# Uav_V1.net
KiCad netlist of a schematic drawn in Altium Designer
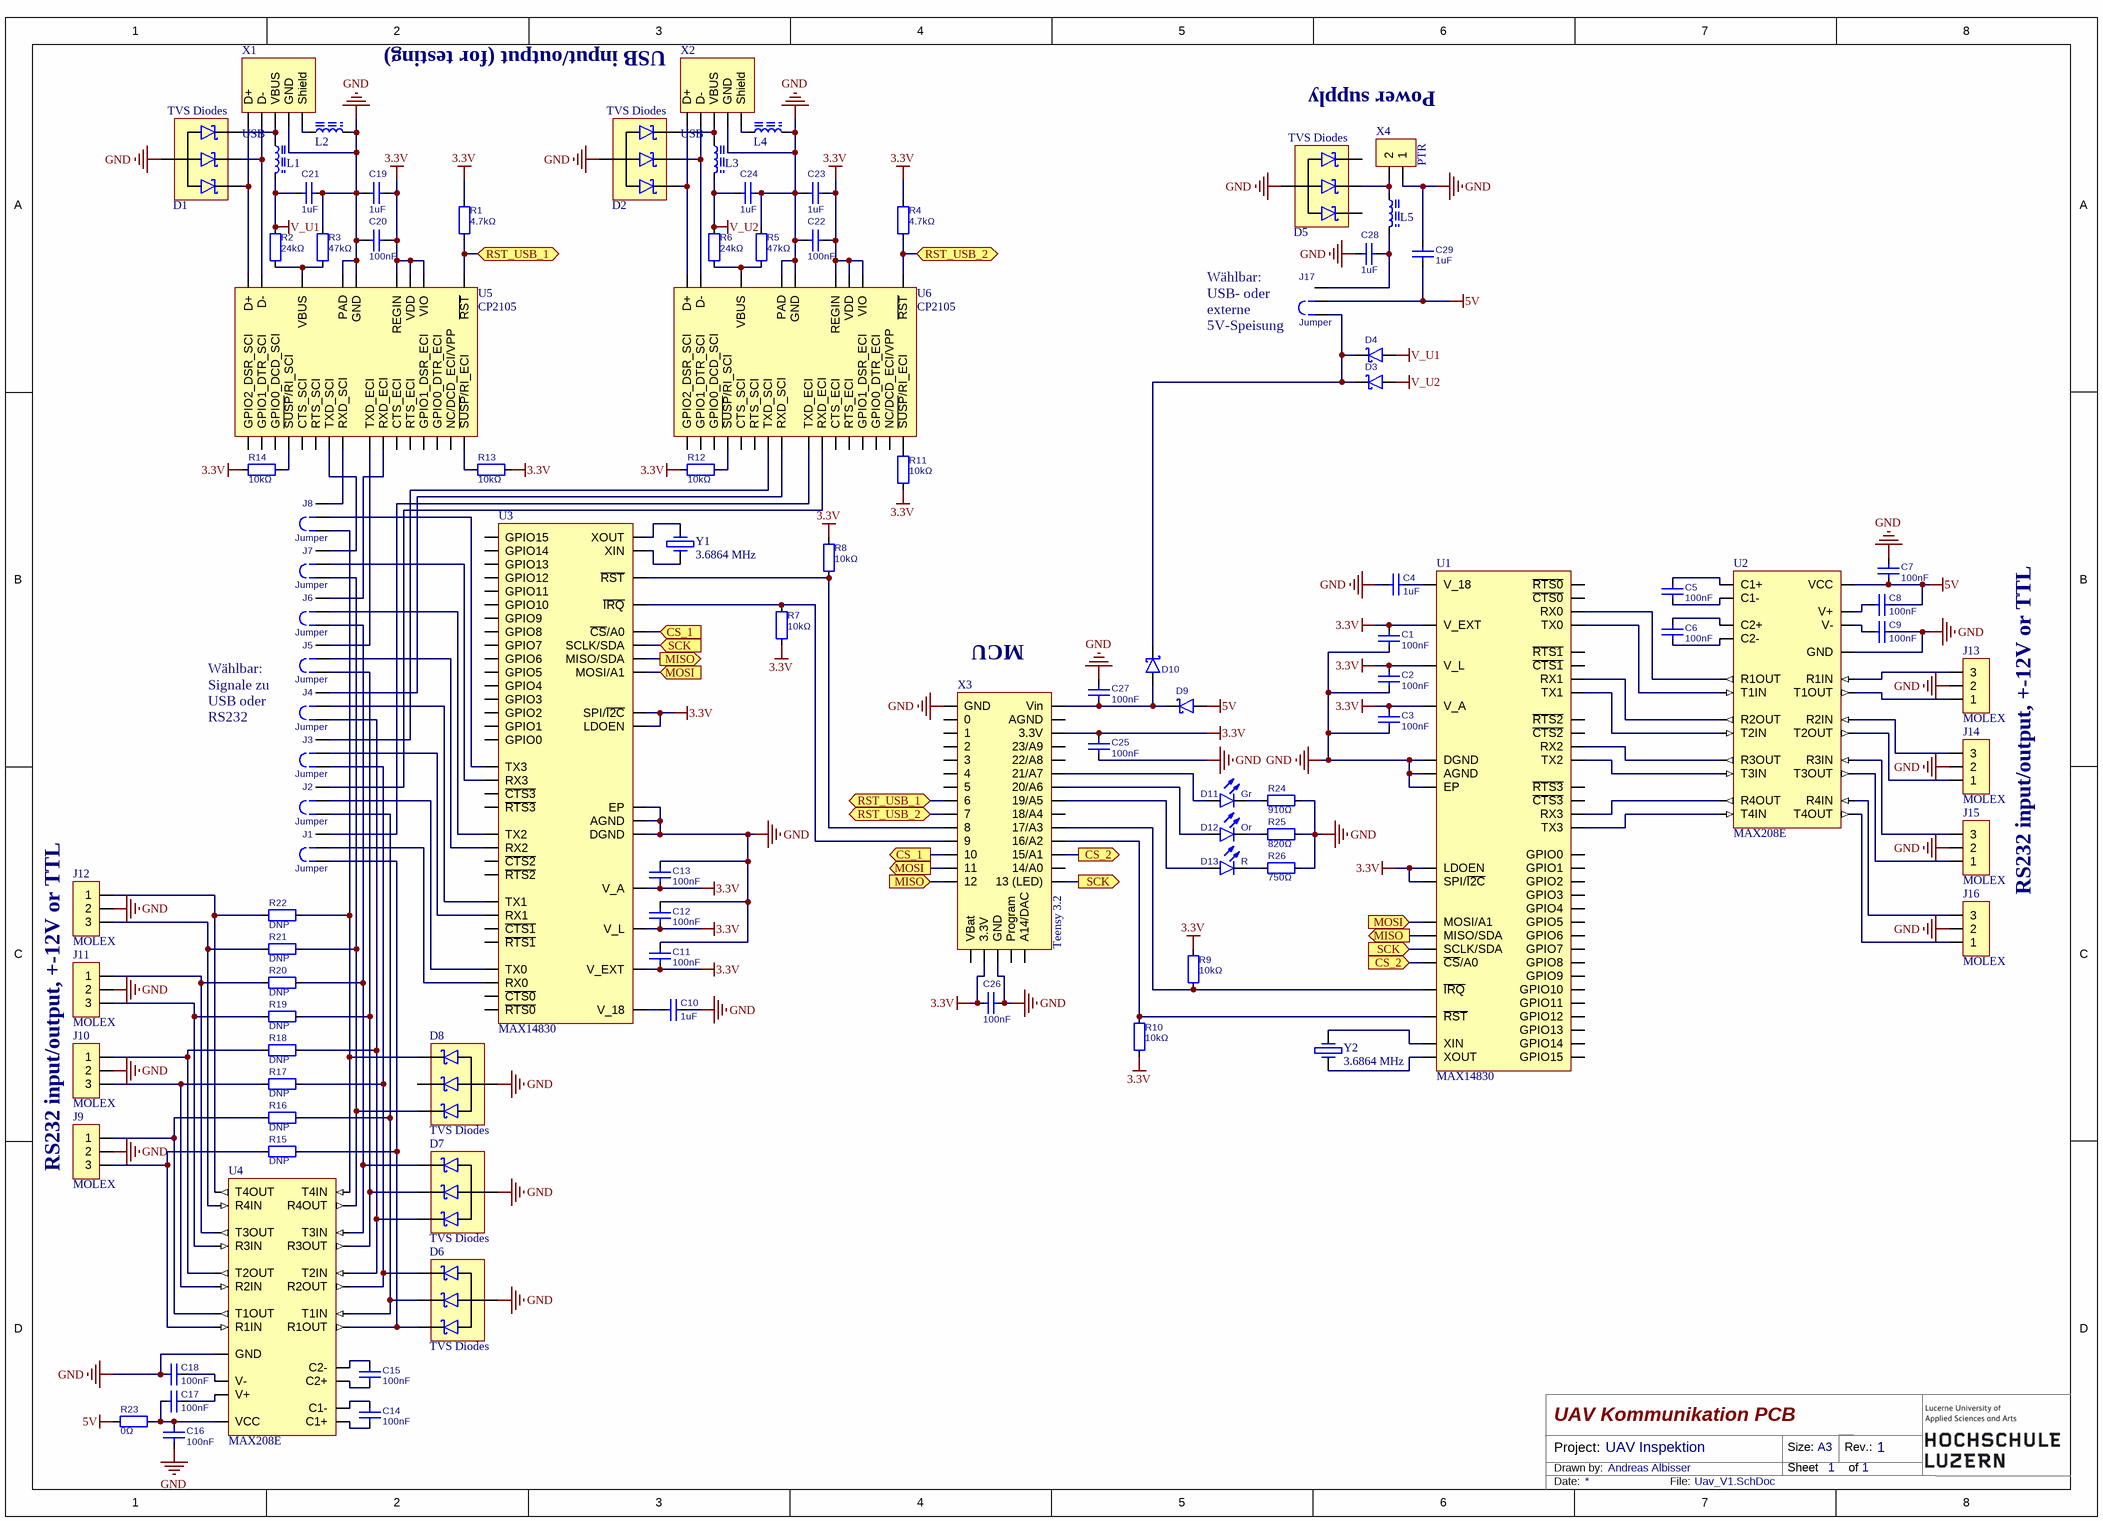
[diagram p0: Uav_V1.SchDoc]

(export (version "E")
  (design (tool "Eeschema 10.0.6"))
  (components
    (comp (ref "C1")
      (value "100nF")
      (footprint "0603")
      (description "Keramikkondensator 0603")
      (fields (field (name "CHANGED BY") "taalbiss"))
      (libsource (lib "CCE_Database_Libs") (part "C_Normal"))
    )
    (comp (ref "C2")
      (value "100nF")
      (footprint "0603")
      (description "Keramikkondensator 0603")
      (fields (field (name "CHANGED BY") "taalbiss"))
      (libsource (lib "CCE_Database_Libs") (part "C_Normal"))
    )
    (comp (ref "C3")
      (value "100nF")
      (footprint "0603")
      (description "Keramikkondensator 0603")
      (fields (field (name "CHANGED BY") "taalbiss"))
      (libsource (lib "CCE_Database_Libs") (part "C_Normal"))
    )
    (comp (ref "C4")
      (value "1uF")
      (footprint "0603")
      (description "Keramikkondensator 0603")
      (fields (field (name "CHANGED BY") "taalbiss"))
      (libsource (lib "CCE_Database_Libs") (part "C_Normal"))
    )
    (comp (ref "C5")
      (value "100nF")
      (footprint "0603")
      (description "Keramikkondensator 0603")
      (fields (field (name "CHANGED BY") "taalbiss"))
      (libsource (lib "CCE_Database_Libs") (part "C_Normal"))
    )
    (comp (ref "C6")
      (value "100nF")
      (footprint "0603")
      (description "Keramikkondensator 0603")
      (fields (field (name "CHANGED BY") "taalbiss"))
      (libsource (lib "CCE_Database_Libs") (part "C_Normal"))
    )
    (comp (ref "C7")
      (value "100nF")
      (footprint "0603")
      (description "Keramikkondensator 0603")
      (fields (field (name "CHANGED BY") "taalbiss"))
      (libsource (lib "CCE_Database_Libs") (part "C_Normal"))
    )
    (comp (ref "C8")
      (value "100nF")
      (footprint "0603")
      (description "Keramikkondensator 0603")
      (fields (field (name "CHANGED BY") "taalbiss"))
      (libsource (lib "CCE_Database_Libs") (part "C_Normal"))
    )
    (comp (ref "C9")
      (value "100nF")
      (footprint "0603")
      (description "Keramikkondensator 0603")
      (fields (field (name "CHANGED BY") "taalbiss"))
      (libsource (lib "CCE_Database_Libs") (part "C_Normal"))
    )
    (comp (ref "C10")
      (value "1uF")
      (footprint "0603")
      (description "Keramikkondensator 0603")
      (fields (field (name "CHANGED BY") "taalbiss"))
      (libsource (lib "CCE_Database_Libs") (part "C_Normal"))
    )
    (comp (ref "C11")
      (value "100nF")
      (footprint "0603")
      (description "Keramikkondensator 0603")
      (fields (field (name "CHANGED BY") "taalbiss"))
      (libsource (lib "CCE_Database_Libs") (part "C_Normal"))
    )
    (comp (ref "C12")
      (value "100nF")
      (footprint "0603")
      (description "Keramikkondensator 0603")
      (fields (field (name "CHANGED BY") "taalbiss"))
      (libsource (lib "CCE_Database_Libs") (part "C_Normal"))
    )
    (comp (ref "C13")
      (value "100nF")
      (footprint "0603")
      (description "Keramikkondensator 0603")
      (fields (field (name "CHANGED BY") "taalbiss"))
      (libsource (lib "CCE_Database_Libs") (part "C_Normal"))
    )
    (comp (ref "C14")
      (value "100nF")
      (footprint "0603")
      (description "Keramikkondensator 0603")
      (fields (field (name "CHANGED BY") "taalbiss"))
      (libsource (lib "CCE_Database_Libs") (part "C_Normal"))
    )
    (comp (ref "C15")
      (value "100nF")
      (footprint "0603")
      (description "Keramikkondensator 0603")
      (fields (field (name "CHANGED BY") "taalbiss"))
      (libsource (lib "CCE_Database_Libs") (part "C_Normal"))
    )
    (comp (ref "C16")
      (value "100nF")
      (footprint "0603")
      (description "Keramikkondensator 0603")
      (fields (field (name "CHANGED BY") "taalbiss"))
      (libsource (lib "CCE_Database_Libs") (part "C_Normal"))
    )
    (comp (ref "C17")
      (value "100nF")
      (footprint "0603")
      (description "Keramikkondensator 0603")
      (fields (field (name "CHANGED BY") "taalbiss"))
      (libsource (lib "CCE_Database_Libs") (part "C_Normal"))
    )
    (comp (ref "C18")
      (value "100nF")
      (footprint "0603")
      (description "Keramikkondensator 0603")
      (fields (field (name "CHANGED BY") "taalbiss"))
      (libsource (lib "CCE_Database_Libs") (part "C_Normal"))
    )
    (comp (ref "C19")
      (value "1uF")
      (footprint "0603")
      (description "Keramikkondensator 0603")
      (fields (field (name "CHANGED BY") "taalbiss"))
      (libsource (lib "CCE_Database_Libs") (part "C_Normal"))
    )
    (comp (ref "C20")
      (value "100nF")
      (footprint "0603")
      (description "Keramikkondensator 0603")
      (fields (field (name "CHANGED BY") "taalbiss"))
      (libsource (lib "CCE_Database_Libs") (part "C_Normal"))
    )
    (comp (ref "C21")
      (value "1uF")
      (footprint "0603")
      (description "Keramikkondensator 0603")
      (fields (field (name "CHANGED BY") "taalbiss"))
      (libsource (lib "CCE_Database_Libs") (part "C_Normal"))
    )
    (comp (ref "C22")
      (value "100nF")
      (footprint "0603")
      (description "Keramikkondensator 0603")
      (fields (field (name "CHANGED BY") "taalbiss"))
      (libsource (lib "CCE_Database_Libs") (part "C_Normal"))
    )
    (comp (ref "C23")
      (value "1uF")
      (footprint "0603")
      (description "Keramikkondensator 0603")
      (fields (field (name "CHANGED BY") "taalbiss"))
      (libsource (lib "CCE_Database_Libs") (part "C_Normal"))
    )
    (comp (ref "C24")
      (value "1uF")
      (footprint "0603")
      (description "Keramikkondensator 0603")
      (fields (field (name "CHANGED BY") "taalbiss"))
      (libsource (lib "CCE_Database_Libs") (part "C_Normal"))
    )
    (comp (ref "C25")
      (value "100nF")
      (footprint "0603")
      (description "Keramikkondensator 0603")
      (fields (field (name "CHANGED BY") "taalbiss"))
      (libsource (lib "CCE_Database_Libs") (part "C_Normal"))
    )
    (comp (ref "C26")
      (value "100nF")
      (footprint "0603")
      (description "Keramikkondensator 0603")
      (fields (field (name "CHANGED BY") "taalbiss"))
      (libsource (lib "CCE_Database_Libs") (part "C_Normal"))
    )
    (comp (ref "C27")
      (value "100nF")
      (footprint "0603")
      (description "Keramikkondensator 0603")
      (fields (field (name "CHANGED BY") "taalbiss"))
      (libsource (lib "CCE_Database_Libs") (part "C_Normal"))
    )
    (comp (ref "C28")
      (value "1uF")
      (footprint "0603")
      (description "Keramikkondensator 0603")
      (fields (field (name "CHANGED BY") "taalbiss"))
      (libsource (lib "CCE_Database_Libs") (part "C_Normal"))
    )
    (comp (ref "C29")
      (value "1uF")
      (footprint "0603")
      (description "Keramikkondensator 0603")
      (fields (field (name "CHANGED BY") "taalbiss"))
      (libsource (lib "CCE_Database_Libs") (part "C_Normal"))
    )
    (comp (ref "D1")
      (value "TVS Diodes")
      (footprint "UAV:SOT-143-4")
      (libsource (lib "") (part "TVS_Diode_3fach_1"))
    )
    (comp (ref "D2")
      (value "TVS Diodes")
      (footprint "UAV:SOT-143-4")
      (libsource (lib "") (part "TVS_Diode_3fach_1"))
    )
    (comp (ref "D3")
      (value "?")
      (footprint "SOD-123")
      (description "Schottky Diode SOD-123")
      (fields (field (name "CHANGED BY") "taalbiss"))
      (libsource (lib "CCE_Database_Libs") (part "Diode_Schottky"))
    )
    (comp (ref "D4")
      (value "?")
      (footprint "SOD-123")
      (description "Schottky Diode SOD-123")
      (fields (field (name "CHANGED BY") "taalbiss"))
      (libsource (lib "CCE_Database_Libs") (part "Diode_Schottky"))
    )
    (comp (ref "D5")
      (value "TVS Diodes")
      (footprint "UAV:SOT-143-4")
      (libsource (lib "") (part "TVS_Diode_3fach_1"))
    )
    (comp (ref "D6")
      (value "TVS Diodes")
      (footprint "UAV:SOT-143-4")
      (libsource (lib "UAV") (part "TVS_Diode_3fach"))
    )
    (comp (ref "D7")
      (value "TVS Diodes")
      (footprint "UAV:SOT-143-4")
      (libsource (lib "UAV") (part "TVS_Diode_3fach"))
    )
    (comp (ref "D8")
      (value "TVS Diodes")
      (footprint "UAV:SOT-143-4")
      (libsource (lib "UAV") (part "TVS_Diode_3fach"))
    )
    (comp (ref "D9")
      (value "?")
      (footprint "SOD-123")
      (description "Schottky Diode SOD-123")
      (fields (field (name "CHANGED BY") "taalbiss"))
      (libsource (lib "CCE_Database_Libs") (part "Diode_Schottky"))
    )
    (comp (ref "D10")
      (value "?")
      (footprint "SOD-123")
      (description "Schottky Diode SOD-123")
      (fields (field (name "CHANGED BY") "taalbiss"))
      (libsource (lib "CCE_Database_Libs") (part "Diode_Schottky"))
    )
    (comp (ref "D11")
      (value "Gr")
      (footprint "0603D")
      (description "LED SMD 0603")
      (fields (field (name "CHANGED BY") "taalbiss"))
      (libsource (lib "CCE_Database_Libs") (part "LED"))
    )
    (comp (ref "D12")
      (value "Or")
      (footprint "0603D")
      (description "LED SMD 0603")
      (fields (field (name "CHANGED BY") "taalbiss"))
      (libsource (lib "CCE_Database_Libs") (part "LED"))
    )
    (comp (ref "D13")
      (value "R")
      (footprint "0603D")
      (description "LED SMD 0603")
      (fields (field (name "CHANGED BY") "taalbiss"))
      (libsource (lib "CCE_Database_Libs") (part "LED"))
    )
    (comp (ref "J1")
      (value "Jumper")
      (footprint "Header2,54mm_1x3")
      (description "Jumper THT 2.54mm 1x3")
      (fields (field (name "CHANGED BY") "taalbiss"))
      (libsource (lib "CCE_Database_Libs") (part "Jumper_1x3"))
    )
    (comp (ref "J2")
      (value "Jumper")
      (footprint "Header2,54mm_1x3")
      (description "Jumper THT 2.54mm 1x3")
      (fields (field (name "CHANGED BY") "taalbiss"))
      (libsource (lib "CCE_Database_Libs") (part "Jumper_1x3"))
    )
    (comp (ref "J3")
      (value "Jumper")
      (footprint "Header2,54mm_1x3")
      (description "Jumper THT 2.54mm 1x3")
      (fields (field (name "CHANGED BY") "taalbiss"))
      (libsource (lib "CCE_Database_Libs") (part "Jumper_1x3"))
    )
    (comp (ref "J4")
      (value "Jumper")
      (footprint "Header2,54mm_1x3")
      (description "Jumper THT 2.54mm 1x3")
      (fields (field (name "CHANGED BY") "taalbiss"))
      (libsource (lib "CCE_Database_Libs") (part "Jumper_1x3"))
    )
    (comp (ref "J5")
      (value "Jumper")
      (footprint "Header2,54mm_1x3")
      (description "Jumper THT 2.54mm 1x3")
      (fields (field (name "CHANGED BY") "taalbiss"))
      (libsource (lib "CCE_Database_Libs") (part "Jumper_1x3"))
    )
    (comp (ref "J6")
      (value "Jumper")
      (footprint "Header2,54mm_1x3")
      (description "Jumper THT 2.54mm 1x3")
      (fields (field (name "CHANGED BY") "taalbiss"))
      (libsource (lib "CCE_Database_Libs") (part "Jumper_1x3"))
    )
    (comp (ref "J7")
      (value "Jumper")
      (footprint "Header2,54mm_1x3")
      (description "Jumper THT 2.54mm 1x3")
      (fields (field (name "CHANGED BY") "taalbiss"))
      (libsource (lib "CCE_Database_Libs") (part "Jumper_1x3"))
    )
    (comp (ref "J8")
      (value "Jumper")
      (footprint "Header2,54mm_1x3")
      (description "Jumper THT 2.54mm 1x3")
      (fields (field (name "CHANGED BY") "taalbiss"))
      (libsource (lib "CCE_Database_Libs") (part "Jumper_1x3"))
    )
    (comp (ref "J9") (value "MOLEX") (footprint "UAV:MOLEX_1x3") (libsource (lib "") (part "Header_1x3_1")))
    (comp (ref "J10") (value "MOLEX") (footprint "UAV:MOLEX_1x3") (libsource (lib "") (part "Header_1x3_1")))
    (comp (ref "J11") (value "MOLEX") (footprint "UAV:MOLEX_1x3") (libsource (lib "") (part "Header_1x3_1")))
    (comp (ref "J12") (value "MOLEX") (footprint "UAV:MOLEX_1x3") (libsource (lib "") (part "Header_1x3_1")))
    (comp (ref "J13") (value "MOLEX") (footprint "UAV:MOLEX_1x3") (libsource (lib "UAV") (part "Header_1x3")))
    (comp (ref "J14") (value "MOLEX") (footprint "UAV:MOLEX_1x3") (libsource (lib "UAV") (part "Header_1x3")))
    (comp (ref "J15") (value "MOLEX") (footprint "UAV:MOLEX_1x3") (libsource (lib "UAV") (part "Header_1x3")))
    (comp (ref "J16") (value "MOLEX") (footprint "UAV:MOLEX_1x3") (libsource (lib "UAV") (part "Header_1x3")))
    (comp (ref "J17")
      (value "Jumper")
      (footprint "Header2,54mm_1x3")
      (description "Jumper THT 2.54mm 1x3")
      (fields (field (name "CHANGED BY") "taalbiss"))
      (libsource (lib "CCE_Database_Libs") (part "Jumper_1x3"))
    )
    (comp (ref "L1")
      (value "MPZ1608S601A")
      (footprint "0603")
      (description "Ferrit 0603")
      (fields (field (name "CHANGED BY") "taalbiss"))
      (libsource (lib "CCE_Database_Libs") (part "L_Ferrite"))
    )
    (comp (ref "L2")
      (value "MPZ1608S601A")
      (footprint "0603")
      (description "Ferrit 0603")
      (fields (field (name "CHANGED BY") "taalbiss"))
      (libsource (lib "CCE_Database_Libs") (part "L_Ferrite"))
    )
    (comp (ref "L3")
      (value "MPZ1608S601A")
      (footprint "0603")
      (description "Ferrit 0603")
      (fields (field (name "CHANGED BY") "taalbiss"))
      (libsource (lib "CCE_Database_Libs") (part "L_Ferrite"))
    )
    (comp (ref "L4")
      (value "MPZ1608S601A")
      (footprint "0603")
      (description "Ferrit 0603")
      (fields (field (name "CHANGED BY") "taalbiss"))
      (libsource (lib "CCE_Database_Libs") (part "L_Ferrite"))
    )
    (comp (ref "L5")
      (value "MPZ1608S601A")
      (footprint "0603")
      (description "Ferrit 0603")
      (fields (field (name "CHANGED BY") "taalbiss"))
      (libsource (lib "CCE_Database_Libs") (part "L_Ferrite"))
    )
    (comp (ref "R1")
      (value "4.7kΩ")
      (footprint "0603")
      (description "Widerstand 0603")
      (fields (field (name "CHANGED BY") "taalbiss"))
      (libsource (lib "") (part "R_Normal_1"))
    )
    (comp (ref "R2")
      (value "24kΩ")
      (footprint "0603")
      (description "Widerstand 0603")
      (fields (field (name "CHANGED BY") "taalbiss"))
      (libsource (lib "CCE_Database_Libs") (part "R_Normal"))
    )
    (comp (ref "R3")
      (value "47kΩ")
      (footprint "0603")
      (description "Widerstand 0603")
      (fields (field (name "CHANGED BY") "taalbiss"))
      (libsource (lib "CCE_Database_Libs") (part "R_Normal"))
    )
    (comp (ref "R4")
      (value "4.7kΩ")
      (footprint "0603")
      (description "Widerstand 0603")
      (fields (field (name "CHANGED BY") "taalbiss"))
      (libsource (lib "") (part "R_Normal_1"))
    )
    (comp (ref "R5")
      (value "47kΩ")
      (footprint "0603")
      (description "Widerstand 0603")
      (fields (field (name "CHANGED BY") "taalbiss"))
      (libsource (lib "CCE_Database_Libs") (part "R_Normal"))
    )
    (comp (ref "R6")
      (value "24kΩ")
      (footprint "0603")
      (description "Widerstand 0603")
      (fields (field (name "CHANGED BY") "taalbiss"))
      (libsource (lib "CCE_Database_Libs") (part "R_Normal"))
    )
    (comp (ref "R7")
      (value "10kΩ")
      (footprint "0603")
      (description "Widerstand 0603")
      (fields (field (name "CHANGED BY") "taalbiss"))
      (libsource (lib "") (part "R_Normal_1"))
    )
    (comp (ref "R8")
      (value "10kΩ")
      (footprint "0603")
      (description "Widerstand 0603")
      (fields (field (name "CHANGED BY") "taalbiss"))
      (libsource (lib "") (part "R_Normal_1"))
    )
    (comp (ref "R9")
      (value "10kΩ")
      (footprint "0603")
      (description "Widerstand 0603")
      (fields (field (name "CHANGED BY") "taalbiss"))
      (libsource (lib "") (part "R_Normal_1"))
    )
    (comp (ref "R10")
      (value "10kΩ")
      (footprint "0603")
      (description "Widerstand 0603")
      (fields (field (name "CHANGED BY") "taalbiss"))
      (libsource (lib "") (part "R_Normal_1"))
    )
    (comp (ref "R11")
      (value "10kΩ")
      (footprint "0603")
      (description "Widerstand 0603")
      (fields (field (name "CHANGED BY") "taalbiss"))
      (libsource (lib "") (part "R_Normal_1"))
    )
    (comp (ref "R12")
      (value "10kΩ")
      (footprint "0603")
      (description "Widerstand 0603")
      (fields (field (name "CHANGED BY") "taalbiss"))
      (libsource (lib "") (part "R_Normal_2"))
    )
    (comp (ref "R13")
      (value "10kΩ")
      (footprint "0603")
      (description "Widerstand 0603")
      (fields (field (name "CHANGED BY") "taalbiss"))
      (libsource (lib "") (part "R_Normal_2"))
    )
    (comp (ref "R14")
      (value "10kΩ")
      (footprint "0603")
      (description "Widerstand 0603")
      (fields (field (name "CHANGED BY") "taalbiss"))
      (libsource (lib "") (part "R_Normal_2"))
    )
    (comp (ref "R15")
      (value "DNP")
      (footprint "0603")
      (description "Widerstand 0603")
      (fields (field (name "CHANGED BY") "taalbiss"))
      (libsource (lib "") (part "R_Normal_2"))
    )
    (comp (ref "R16")
      (value "DNP")
      (footprint "0603")
      (description "Widerstand 0603")
      (fields (field (name "CHANGED BY") "taalbiss"))
      (libsource (lib "") (part "R_Normal_2"))
    )
    (comp (ref "R17")
      (value "DNP")
      (footprint "0603")
      (description "Widerstand 0603")
      (fields (field (name "CHANGED BY") "taalbiss"))
      (libsource (lib "") (part "R_Normal_2"))
    )
    (comp (ref "R18")
      (value "DNP")
      (footprint "0603")
      (description "Widerstand 0603")
      (fields (field (name "CHANGED BY") "taalbiss"))
      (libsource (lib "") (part "R_Normal_2"))
    )
    (comp (ref "R19")
      (value "DNP")
      (footprint "0603")
      (description "Widerstand 0603")
      (fields (field (name "CHANGED BY") "taalbiss"))
      (libsource (lib "") (part "R_Normal_2"))
    )
    (comp (ref "R20")
      (value "DNP")
      (footprint "0603")
      (description "Widerstand 0603")
      (fields (field (name "CHANGED BY") "taalbiss"))
      (libsource (lib "") (part "R_Normal_2"))
    )
    (comp (ref "R21")
      (value "DNP")
      (footprint "0603")
      (description "Widerstand 0603")
      (fields (field (name "CHANGED BY") "taalbiss"))
      (libsource (lib "") (part "R_Normal_2"))
    )
    (comp (ref "R22")
      (value "DNP")
      (footprint "0603")
      (description "Widerstand 0603")
      (fields (field (name "CHANGED BY") "taalbiss"))
      (libsource (lib "") (part "R_Normal_2"))
    )
    (comp (ref "R23")
      (value "0Ω")
      (footprint "0603")
      (description "Widerstand 0603")
      (fields (field (name "CHANGED BY") "taalbiss"))
      (libsource (lib "") (part "R_Normal_2"))
    )
    (comp (ref "R24")
      (value "910Ω")
      (footprint "0603")
      (description "Widerstand 0603")
      (fields (field (name "CHANGED BY") "taalbiss"))
      (libsource (lib "") (part "R_Normal_2"))
    )
    (comp (ref "R25")
      (value "820Ω")
      (footprint "0603")
      (description "Widerstand 0603")
      (fields (field (name "CHANGED BY") "taalbiss"))
      (libsource (lib "") (part "R_Normal_2"))
    )
    (comp (ref "R26")
      (value "750Ω")
      (footprint "0603")
      (description "Widerstand 0603")
      (fields (field (name "CHANGED BY") "taalbiss"))
      (libsource (lib "") (part "R_Normal_2"))
    )
    (comp (ref "U1") (value "MAX14830") (footprint "UAV:TQFN48") (libsource (lib "UAV") (part "MAX14830")))
    (comp (ref "U2") (value "MAX208E") (footprint "UAV:SSOP24") (libsource (lib "UAV") (part "MAX208E")))
    (comp (ref "U3") (value "MAX14830") (footprint "UAV:TQFN48") (libsource (lib "") (part "MAX14830_1")))
    (comp (ref "U4") (value "MAX208E") (footprint "UAV:SSOP24") (libsource (lib "") (part "MAX208E_1")))
    (comp (ref "U5") (value "CP2105") (footprint "UAV:QFN24") (libsource (lib "UAV") (part "CP2105")))
    (comp (ref "U6") (value "CP2105") (footprint "UAV:QFN24") (libsource (lib "UAV") (part "CP2105")))
    (comp (ref "X1") (value "USB") (footprint "UAV:USB_Mini_TypB") (libsource (lib "UAV") (part "USB")))
    (comp (ref "X2") (value "USB") (footprint "UAV:USB_Mini_TypB") (libsource (lib "UAV") (part "USB")))
    (comp (ref "X3")
      (value "Teensy 3.2")
      (footprint "UAV:Teensy_3_2")
      (libsource (lib "UAV") (part "Teensy_3_2"))
    )
    (comp (ref "X4") (value "PTR") (footprint "UAV:PTR_1X2") (libsource (lib "UAV") (part "Header_1x2")))
    (comp (ref "Y1")
      (value "3.6864 MHz")
      (footprint "UAV:Crystal_10x4_5mm")
      (libsource (lib "UAV") (part "Crystal_3_6864_MHz"))
    )
    (comp (ref "Y2")
      (value "3.6864 MHz")
      (footprint "UAV:Crystal_10x4_5mm")
      (libsource (lib "UAV") (part "Crystal_3_6864_MHz"))
    )
  )
  (nets
    (net (code "1") (name "/CS_1") (class "Default")
      (node (ref "U3") (pin "5") (pinfunction "~{CS}/A0_5") (pintype "passive"))
      (node (ref "X3") (pin "10") (pinfunction "10_10") (pintype "passive"))
    )
    (net (code "2") (name "/CS_2") (class "Default")
      (node (ref "U1") (pin "5") (pinfunction "~{CS}/A0_5") (pintype "passive"))
      (node (ref "X3") (pin "15") (pinfunction "15/A1_15") (pintype "passive"))
    )
    (net (code "3") (name "/MISO") (class "Default")
      (node (ref "U1") (pin "3") (pinfunction "MISO/SDA_3") (pintype "passive"))
      (node (ref "U3") (pin "3") (pinfunction "MISO/SDA_3") (pintype "passive"))
      (node (ref "X3") (pin "12") (pinfunction "12_12") (pintype "passive"))
    )
    (net (code "4") (name "/MOSI") (class "Default")
      (node (ref "U1") (pin "6") (pinfunction "MOSI/A1_6") (pintype "passive"))
      (node (ref "U3") (pin "6") (pinfunction "MOSI/A1_6") (pintype "passive"))
      (node (ref "X3") (pin "11") (pinfunction "11_11") (pintype "passive"))
    )
    (net (code "5") (name "/RST_USB_1") (class "Default")
      (node (ref "R1") (pin "1") (pinfunction "1_1") (pintype "passive"))
      (node (ref "U5") (pin "9") (pinfunction "~{RST}_9") (pintype "passive"))
      (node (ref "X3") (pin "6") (pinfunction "6_6") (pintype "passive"))
    )
    (net (code "6") (name "/RST_USB_2") (class "Default")
      (node (ref "R4") (pin "1") (pinfunction "1_1") (pintype "passive"))
      (node (ref "U6") (pin "9") (pinfunction "~{RST}_9") (pintype "passive"))
      (node (ref "X3") (pin "7") (pinfunction "7_7") (pintype "passive"))
    )
    (net (code "7") (name "/SCK") (class "Default")
      (node (ref "U1") (pin "4") (pinfunction "SCLK/SDA_4") (pintype "passive"))
      (node (ref "U3") (pin "4") (pinfunction "SCLK/SDA_4") (pintype "passive"))
      (node (ref "X3") (pin "13") (pinfunction "13_(LED)_13") (pintype "passive"))
    )
    (net (code "8") (name "3.3V") (class "Default")
      (node (ref "C1") (pin "2") (pinfunction "2_2") (pintype "passive"))
      (node (ref "C11") (pin "2") (pinfunction "2_2") (pintype "passive"))
      (node (ref "C12") (pin "2") (pinfunction "2_2") (pintype "passive"))
      (node (ref "C13") (pin "2") (pinfunction "2_2") (pintype "passive"))
      (node (ref "C19") (pin "1") (pinfunction "1_1") (pintype "passive"))
      (node (ref "C2") (pin "2") (pinfunction "2_2") (pintype "passive"))
      (node (ref "C20") (pin "1") (pinfunction "1_1") (pintype "passive"))
      (node (ref "C22") (pin "1") (pinfunction "1_1") (pintype "passive"))
      (node (ref "C23") (pin "1") (pinfunction "1_1") (pintype "passive"))
      (node (ref "C25") (pin "1") (pinfunction "1_1") (pintype "passive"))
      (node (ref "C26") (pin "1") (pinfunction "1_1") (pintype "passive"))
      (node (ref "C3") (pin "2") (pinfunction "2_2") (pintype "passive"))
      (node (ref "R1") (pin "2") (pinfunction "2_2") (pintype "passive"))
      (node (ref "R10") (pin "1") (pinfunction "1_1") (pintype "passive"))
      (node (ref "R11") (pin "1") (pinfunction "1_1") (pintype "passive"))
      (node (ref "R12") (pin "2") (pinfunction "2_2") (pintype "passive"))
      (node (ref "R13") (pin "1") (pinfunction "1_1") (pintype "passive"))
      (node (ref "R14") (pin "2") (pinfunction "2_2") (pintype "passive"))
      (node (ref "R4") (pin "2") (pinfunction "2_2") (pintype "passive"))
      (node (ref "R7") (pin "1") (pinfunction "1_1") (pintype "passive"))
      (node (ref "R8") (pin "2") (pinfunction "2_2") (pintype "passive"))
      (node (ref "R9") (pin "2") (pinfunction "2_2") (pintype "passive"))
      (node (ref "U1") (pin "1") (pinfunction "SPI/~{I2C}_1") (pintype "passive"))
      (node (ref "U1") (pin "2") (pinfunction "LDOEN_2") (pintype "passive"))
      (node (ref "U1") (pin "43") (pinfunction "V_EXT_43") (pintype "passive"))
      (node (ref "U1") (pin "47") (pinfunction "V_A_47") (pintype "passive"))
      (node (ref "U1") (pin "9") (pinfunction "V_L_9") (pintype "passive"))
      (node (ref "U3") (pin "1") (pinfunction "SPI/~{I2C}_1") (pintype "passive"))
      (node (ref "U3") (pin "2") (pinfunction "LDOEN_2") (pintype "passive"))
      (node (ref "U3") (pin "43") (pinfunction "V_EXT_43") (pintype "passive"))
      (node (ref "U3") (pin "47") (pinfunction "V_A_47") (pintype "passive"))
      (node (ref "U3") (pin "9") (pinfunction "V_L_9") (pintype "passive"))
      (node (ref "U5") (pin "5") (pinfunction "VIO_5") (pintype "passive"))
      (node (ref "U5") (pin "6") (pinfunction "VDD_6") (pintype "passive"))
      (node (ref "U5") (pin "7") (pinfunction "REGIN_7") (pintype "passive"))
      (node (ref "U6") (pin "5") (pinfunction "VIO_5") (pintype "passive"))
      (node (ref "U6") (pin "6") (pinfunction "VDD_6") (pintype "passive"))
      (node (ref "U6") (pin "7") (pinfunction "REGIN_7") (pintype "passive"))
      (node (ref "X3") (pin "3.3V_1") (pinfunction "3.3V_3.3V_1") (pintype "passive"))
      (node (ref "X3") (pin "3.3V_2") (pinfunction "3.3V_3.3V_2") (pintype "passive"))
    )
    (net (code "9") (name "5V") (class "Default")
      (node (ref "C29") (pin "1") (pinfunction "1_1") (pintype "passive"))
      (node (ref "C7") (pin "1") (pinfunction "1_1") (pintype "passive"))
      (node (ref "C8") (pin "1") (pinfunction "1_1") (pintype "passive"))
      (node (ref "D9") (pin "1") (pinfunction "A_1") (pintype "passive"))
      (node (ref "J17") (pin "2") (pinfunction "2_2") (pintype "passive"))
      (node (ref "R23") (pin "2") (pinfunction "2_2") (pintype "passive"))
      (node (ref "U2") (pin "9") (pinfunction "VCC_9") (pintype "passive"))
    )
    (net (code "10") (name "GND") (class "Default")
      (node (ref "C1") (pin "1") (pinfunction "1_1") (pintype "passive"))
      (node (ref "C10") (pin "1") (pinfunction "1_1") (pintype "passive"))
      (node (ref "C11") (pin "1") (pinfunction "1_1") (pintype "passive"))
      (node (ref "C12") (pin "1") (pinfunction "1_1") (pintype "passive"))
      (node (ref "C13") (pin "1") (pinfunction "1_1") (pintype "passive"))
      (node (ref "C16") (pin "2") (pinfunction "2_2") (pintype "passive"))
      (node (ref "C18") (pin "1") (pinfunction "1_1") (pintype "passive"))
      (node (ref "C19") (pin "2") (pinfunction "2_2") (pintype "passive"))
      (node (ref "C2") (pin "1") (pinfunction "1_1") (pintype "passive"))
      (node (ref "C20") (pin "2") (pinfunction "2_2") (pintype "passive"))
      (node (ref "C21") (pin "1") (pinfunction "1_1") (pintype "passive"))
      (node (ref "C22") (pin "2") (pinfunction "2_2") (pintype "passive"))
      (node (ref "C23") (pin "2") (pinfunction "2_2") (pintype "passive"))
      (node (ref "C24") (pin "1") (pinfunction "1_1") (pintype "passive"))
      (node (ref "C25") (pin "2") (pinfunction "2_2") (pintype "passive"))
      (node (ref "C26") (pin "2") (pinfunction "2_2") (pintype "passive"))
      (node (ref "C27") (pin "1") (pinfunction "1_1") (pintype "passive"))
      (node (ref "C28") (pin "2") (pinfunction "2_2") (pintype "passive"))
      (node (ref "C29") (pin "2") (pinfunction "2_2") (pintype "passive"))
      (node (ref "C3") (pin "1") (pinfunction "1_1") (pintype "passive"))
      (node (ref "C4") (pin "1") (pinfunction "1_1") (pintype "passive"))
      (node (ref "C7") (pin "2") (pinfunction "2_2") (pintype "passive"))
      (node (ref "C9") (pin "1") (pinfunction "1_1") (pintype "passive"))
      (node (ref "D1") (pin "1") (pinfunction "CA_1") (pintype "passive"))
      (node (ref "D2") (pin "1") (pinfunction "CA_1") (pintype "passive"))
      (node (ref "D5") (pin "1") (pinfunction "CA_1") (pintype "passive"))
      (node (ref "D6") (pin "1") (pinfunction "CA_1") (pintype "passive"))
      (node (ref "D7") (pin "1") (pinfunction "CA_1") (pintype "passive"))
      (node (ref "D8") (pin "1") (pinfunction "CA_1") (pintype "passive"))
      (node (ref "J10") (pin "2") (pinfunction "2_2") (pintype "passive"))
      (node (ref "J11") (pin "2") (pinfunction "2_2") (pintype "passive"))
      (node (ref "J12") (pin "2") (pinfunction "2_2") (pintype "passive"))
      (node (ref "J13") (pin "2") (pinfunction "2_2") (pintype "passive"))
      (node (ref "J14") (pin "2") (pinfunction "2_2") (pintype "passive"))
      (node (ref "J15") (pin "2") (pinfunction "2_2") (pintype "passive"))
      (node (ref "J16") (pin "2") (pinfunction "2_2") (pintype "passive"))
      (node (ref "J9") (pin "2") (pinfunction "2_2") (pintype "passive"))
      (node (ref "L2") (pin "2") (pinfunction "2_2") (pintype "passive"))
      (node (ref "L4") (pin "2") (pinfunction "2_2") (pintype "passive"))
      (node (ref "R24") (pin "1") (pinfunction "1_1") (pintype "passive"))
      (node (ref "R25") (pin "1") (pinfunction "1_1") (pintype "passive"))
      (node (ref "R26") (pin "1") (pinfunction "1_1") (pintype "passive"))
      (node (ref "R3") (pin "1") (pinfunction "1_1") (pintype "passive"))
      (node (ref "R5") (pin "1") (pinfunction "1_1") (pintype "passive"))
      (node (ref "U1") (pin "10") (pinfunction "DGND_10") (pintype "passive"))
      (node (ref "U1") (pin "46") (pinfunction "AGND_46") (pintype "passive"))
      (node (ref "U1") (pin "49") (pinfunction "EP_49") (pintype "passive"))
      (node (ref "U2") (pin "8") (pinfunction "GND_8") (pintype "passive"))
      (node (ref "U3") (pin "10") (pinfunction "DGND_10") (pintype "passive"))
      (node (ref "U3") (pin "46") (pinfunction "AGND_46") (pintype "passive"))
      (node (ref "U3") (pin "49") (pinfunction "EP_49") (pintype "passive"))
      (node (ref "U4") (pin "8") (pinfunction "GND_8") (pintype "passive"))
      (node (ref "U5") (pin "2") (pinfunction "GND_2") (pintype "passive"))
      (node (ref "U5") (pin "25") (pinfunction "PAD_25") (pintype "passive"))
      (node (ref "U6") (pin "2") (pinfunction "GND_2") (pintype "passive"))
      (node (ref "U6") (pin "25") (pinfunction "PAD_25") (pintype "passive"))
      (node (ref "X1") (pin "4") (pinfunction "GND_4") (pintype "passive"))
      (node (ref "X2") (pin "4") (pinfunction "GND_4") (pintype "passive"))
      (node (ref "X3") (pin "GND_1") (pinfunction "GND_GND_1") (pintype "passive"))
      (node (ref "X3") (pin "GND_2") (pinfunction "GND_GND_2") (pintype "passive"))
      (node (ref "X4") (pin "1") (pinfunction "1_1") (pintype "passive"))
    )
    (net (code "11") (name "Net-(C28-Pad1)") (class "Default")
      (node (ref "C28") (pin "1") (pinfunction "1_1") (pintype "passive"))
      (node (ref "J17") (pin "3") (pinfunction "3_3") (pintype "passive"))
      (node (ref "L5") (pin "2") (pinfunction "2_2") (pintype "passive"))
    )
    (net (code "12") (name "Net-(D1-K1)") (class "Default")
      (node (ref "D1") (pin "2") (pinfunction "K1_2") (pintype "passive"))
      (node (ref "U5") (pin "3") (pinfunction "D+_3") (pintype "passive"))
      (node (ref "X1") (pin "3") (pinfunction "D+_3") (pintype "passive"))
    )
    (net (code "13") (name "Net-(D1-K2)") (class "Default")
      (node (ref "D1") (pin "3") (pinfunction "K2_3") (pintype "passive"))
      (node (ref "U5") (pin "4") (pinfunction "D-_4") (pintype "passive"))
      (node (ref "X1") (pin "2") (pinfunction "D-_2") (pintype "passive"))
    )
    (net (code "14") (name "Net-(D1-K3)") (class "Default")
      (node (ref "D1") (pin "4") (pinfunction "K3_4") (pintype "passive"))
      (node (ref "L1") (pin "1") (pinfunction "1_1") (pintype "passive"))
      (node (ref "X1") (pin "1") (pinfunction "VBUS_1") (pintype "passive"))
    )
    (net (code "15") (name "Net-(D2-K1)") (class "Default")
      (node (ref "D2") (pin "2") (pinfunction "K1_2") (pintype "passive"))
      (node (ref "U6") (pin "3") (pinfunction "D+_3") (pintype "passive"))
      (node (ref "X2") (pin "3") (pinfunction "D+_3") (pintype "passive"))
    )
    (net (code "16") (name "Net-(D2-K2)") (class "Default")
      (node (ref "D2") (pin "3") (pinfunction "K2_3") (pintype "passive"))
      (node (ref "U6") (pin "4") (pinfunction "D-_4") (pintype "passive"))
      (node (ref "X2") (pin "2") (pinfunction "D-_2") (pintype "passive"))
    )
    (net (code "17") (name "Net-(D2-K3)") (class "Default")
      (node (ref "D2") (pin "4") (pinfunction "K3_4") (pintype "passive"))
      (node (ref "L3") (pin "1") (pinfunction "1_1") (pintype "passive"))
      (node (ref "X2") (pin "1") (pinfunction "VBUS_1") (pintype "passive"))
    )
    (net (code "18") (name "Net-(D5-K2)") (class "Default")
      (node (ref "D5") (pin "3") (pinfunction "K2_3") (pintype "passive"))
      (node (ref "L5") (pin "1") (pinfunction "1_1") (pintype "passive"))
      (node (ref "X4") (pin "2") (pinfunction "2_2") (pintype "passive"))
    )
    (net (code "19") (name "Net-(D6-K1)") (class "Default")
      (node (ref "D6") (pin "2") (pinfunction "K1_2") (pintype "passive"))
      (node (ref "J3") (pin "1") (pinfunction "1_1") (pintype "passive"))
      (node (ref "R17") (pin "1") (pinfunction "1_1") (pintype "passive"))
      (node (ref "U4") (pin "4") (pinfunction "R2OUT_4") (pintype "output"))
    )
    (net (code "20") (name "Net-(D6-K2)") (class "Default")
      (node (ref "D6") (pin "3") (pinfunction "K2_3") (pintype "passive"))
      (node (ref "J2") (pin "1") (pinfunction "1_1") (pintype "passive"))
      (node (ref "R16") (pin "1") (pinfunction "1_1") (pintype "passive"))
      (node (ref "U4") (pin "5") (pinfunction "T1IN_5") (pintype "input"))
    )
    (net (code "21") (name "Net-(D6-K3)") (class "Default")
      (node (ref "D6") (pin "4") (pinfunction "K3_4") (pintype "passive"))
      (node (ref "J1") (pin "1") (pinfunction "1_1") (pintype "passive"))
      (node (ref "R15") (pin "1") (pinfunction "1_1") (pintype "passive"))
      (node (ref "U4") (pin "6") (pinfunction "R1OUT_6") (pintype "output"))
    )
    (net (code "22") (name "Net-(D7-K1)") (class "Default")
      (node (ref "D7") (pin "2") (pinfunction "K1_2") (pintype "passive"))
      (node (ref "J6") (pin "1") (pinfunction "1_1") (pintype "passive"))
      (node (ref "R20") (pin "1") (pinfunction "1_1") (pintype "passive"))
      (node (ref "U4") (pin "19") (pinfunction "T3IN_19") (pintype "input"))
    )
    (net (code "23") (name "Net-(D7-K2)") (class "Default")
      (node (ref "D7") (pin "3") (pinfunction "K2_3") (pintype "passive"))
      (node (ref "J5") (pin "1") (pinfunction "1_1") (pintype "passive"))
      (node (ref "R19") (pin "1") (pinfunction "1_1") (pintype "passive"))
      (node (ref "U4") (pin "22") (pinfunction "R3OUT_22") (pintype "output"))
    )
    (net (code "24") (name "Net-(D7-K3)") (class "Default")
      (node (ref "D7") (pin "4") (pinfunction "K3_4") (pintype "passive"))
      (node (ref "J4") (pin "1") (pinfunction "1_1") (pintype "passive"))
      (node (ref "R18") (pin "1") (pinfunction "1_1") (pintype "passive"))
      (node (ref "U4") (pin "18") (pinfunction "T2IN_18") (pintype "input"))
    )
    (net (code "25") (name "Net-(D8-K1)") (class "Default")
      (node (ref "D8") (pin "2") (pinfunction "K1_2") (pintype "passive"))
      (node (ref "J8") (pin "1") (pinfunction "1_1") (pintype "passive"))
      (node (ref "R22") (pin "1") (pinfunction "1_1") (pintype "passive"))
      (node (ref "U4") (pin "21") (pinfunction "T4IN_21") (pintype "input"))
    )
    (net (code "26") (name "Net-(D8-K3)") (class "Default")
      (node (ref "D8") (pin "4") (pinfunction "K3_4") (pintype "passive"))
      (node (ref "J7") (pin "1") (pinfunction "1_1") (pintype "passive"))
      (node (ref "R21") (pin "1") (pinfunction "1_1") (pintype "passive"))
      (node (ref "U4") (pin "17") (pinfunction "R4OUT_17") (pintype "output"))
    )
    (net (code "27") (name "Net-(D10-A)") (class "Default")
      (node (ref "C27") (pin "2") (pinfunction "2_2") (pintype "passive"))
      (node (ref "D10") (pin "1") (pinfunction "A_1") (pintype "passive"))
      (node (ref "D9") (pin "2") (pinfunction "K_2") (pintype "passive"))
      (node (ref "X3") (pin "Vin") (pinfunction "Vin_Vin") (pintype "passive"))
    )
    (net (code "28") (name "Net-(D10-K)") (class "Default")
      (node (ref "D10") (pin "2") (pinfunction "K_2") (pintype "passive"))
      (node (ref "D3") (pin "2") (pinfunction "K_2") (pintype "passive"))
      (node (ref "D4") (pin "2") (pinfunction "K_2") (pintype "passive"))
      (node (ref "J17") (pin "1") (pinfunction "1_1") (pintype "passive"))
    )
    (net (code "29") (name "Net-(D11-A)") (class "Default")
      (node (ref "D11") (pin "1") (pinfunction "A_1") (pintype "passive"))
      (node (ref "X3") (pin "21") (pinfunction "21/A7_21") (pintype "passive"))
    )
    (net (code "30") (name "Net-(D11-K)") (class "Default")
      (node (ref "D11") (pin "2") (pinfunction "K_2") (pintype "passive"))
      (node (ref "R24") (pin "2") (pinfunction "2_2") (pintype "passive"))
    )
    (net (code "31") (name "Net-(D12-A)") (class "Default")
      (node (ref "D12") (pin "1") (pinfunction "A_1") (pintype "passive"))
      (node (ref "X3") (pin "20") (pinfunction "20/A6_20") (pintype "passive"))
    )
    (net (code "32") (name "Net-(D12-K)") (class "Default")
      (node (ref "D12") (pin "2") (pinfunction "K_2") (pintype "passive"))
      (node (ref "R25") (pin "2") (pinfunction "2_2") (pintype "passive"))
    )
    (net (code "33") (name "Net-(D13-A)") (class "Default")
      (node (ref "D13") (pin "1") (pinfunction "A_1") (pintype "passive"))
      (node (ref "X3") (pin "19") (pinfunction "19/A5_19") (pintype "passive"))
    )
    (net (code "34") (name "Net-(D13-K)") (class "Default")
      (node (ref "D13") (pin "2") (pinfunction "K_2") (pintype "passive"))
      (node (ref "R26") (pin "2") (pinfunction "2_2") (pintype "passive"))
    )
    (net (code "35") (name "Net-(U1-RX0)") (class "Default")
      (node (ref "U1") (pin "17") (pinfunction "RX0_17") (pintype "passive"))
      (node (ref "U2") (pin "6") (pinfunction "R1OUT_6") (pintype "output"))
    )
    (net (code "36") (name "Net-(U1-RX1)") (class "Default")
      (node (ref "U1") (pin "25") (pinfunction "RX1_25") (pintype "passive"))
      (node (ref "U2") (pin "4") (pinfunction "R2OUT_4") (pintype "output"))
    )
    (net (code "37") (name "Net-(U1-RX2)") (class "Default")
      (node (ref "U1") (pin "33") (pinfunction "RX2_33") (pintype "passive"))
      (node (ref "U2") (pin "22") (pinfunction "R3OUT_22") (pintype "output"))
    )
    (net (code "38") (name "Net-(U1-RX3)") (class "Default")
      (node (ref "U1") (pin "41") (pinfunction "RX3_41") (pintype "passive"))
      (node (ref "U2") (pin "17") (pinfunction "R4OUT_17") (pintype "output"))
    )
    (net (code "39") (name "Net-(U1-TX0)") (class "Default")
      (node (ref "U1") (pin "18") (pinfunction "TX0_18") (pintype "passive"))
      (node (ref "U2") (pin "5") (pinfunction "T1IN_5") (pintype "input"))
    )
    (net (code "40") (name "Net-(U1-TX1)") (class "Default")
      (node (ref "U1") (pin "26") (pinfunction "TX1_26") (pintype "passive"))
      (node (ref "U2") (pin "18") (pinfunction "T2IN_18") (pintype "input"))
    )
    (net (code "41") (name "Net-(U1-TX2)") (class "Default")
      (node (ref "U1") (pin "34") (pinfunction "TX2_34") (pintype "passive"))
      (node (ref "U2") (pin "19") (pinfunction "T3IN_19") (pintype "input"))
    )
    (net (code "42") (name "Net-(U1-TX3)") (class "Default")
      (node (ref "U1") (pin "42") (pinfunction "TX3_42") (pintype "passive"))
      (node (ref "U2") (pin "21") (pinfunction "T4IN_21") (pintype "input"))
    )
    (net (code "43") (name "Net-(U1-V_18)") (class "Default")
      (node (ref "C4") (pin "2") (pinfunction "2_2") (pintype "passive"))
      (node (ref "U1") (pin "48") (pinfunction "V_18_48") (pintype "passive"))
    )
    (net (code "44") (name "Net-(U1-XIN)") (class "Default")
      (node (ref "U1") (pin "45") (pinfunction "XIN_45") (pintype "passive"))
      (node (ref "Y2") (pin "2") (pinfunction "2_2") (pintype "passive"))
    )
    (net (code "45") (name "Net-(U1-XOUT)") (class "Default")
      (node (ref "U1") (pin "44") (pinfunction "XOUT_44") (pintype "passive"))
      (node (ref "Y2") (pin "1") (pinfunction "1_1") (pintype "passive"))
    )
    (net (code "46") (name "Net-(U1-~{IRQ})") (class "Default")
      (node (ref "R9") (pin "1") (pinfunction "1_1") (pintype "passive"))
      (node (ref "U1") (pin "7") (pinfunction "~{IRQ}_7") (pintype "passive"))
      (node (ref "X3") (pin "17") (pinfunction "17/A3_17") (pintype "passive"))
    )
    (net (code "47") (name "Net-(U1-~{RST})") (class "Default")
      (node (ref "R10") (pin "2") (pinfunction "2_2") (pintype "passive"))
      (node (ref "U1") (pin "8") (pinfunction "~{RST}_8") (pintype "passive"))
      (node (ref "X3") (pin "16") (pinfunction "16/A2_16") (pintype "passive"))
    )
    (net (code "48") (name "Net-(U2-C1+)") (class "Default")
      (node (ref "C5") (pin "2") (pinfunction "2_2") (pintype "passive"))
      (node (ref "U2") (pin "10") (pinfunction "C1+_10") (pintype "passive"))
    )
    (net (code "49") (name "Net-(U2-C1-)") (class "Default")
      (node (ref "C5") (pin "1") (pinfunction "1_1") (pintype "passive"))
      (node (ref "U2") (pin "12") (pinfunction "C1-_12") (pintype "passive"))
    )
    (net (code "50") (name "Net-(U2-C2+)") (class "Default")
      (node (ref "C6") (pin "2") (pinfunction "2_2") (pintype "passive"))
      (node (ref "U2") (pin "13") (pinfunction "C2+_13") (pintype "passive"))
    )
    (net (code "51") (name "Net-(U2-C2-)") (class "Default")
      (node (ref "C6") (pin "1") (pinfunction "1_1") (pintype "passive"))
      (node (ref "U2") (pin "14") (pinfunction "C2-_14") (pintype "passive"))
    )
    (net (code "52") (name "Net-(U2-R1IN)") (class "Default")
      (node (ref "J13") (pin "3") (pinfunction "3_3") (pintype "passive"))
      (node (ref "U2") (pin "7") (pinfunction "R1IN_7") (pintype "input"))
    )
    (net (code "53") (name "Net-(U2-R2IN)") (class "Default")
      (node (ref "J14") (pin "3") (pinfunction "3_3") (pintype "passive"))
      (node (ref "U2") (pin "3") (pinfunction "R2IN_3") (pintype "input"))
    )
    (net (code "54") (name "Net-(U2-R3IN)") (class "Default")
      (node (ref "J15") (pin "3") (pinfunction "3_3") (pintype "passive"))
      (node (ref "U2") (pin "23") (pinfunction "R3IN_23") (pintype "input"))
    )
    (net (code "55") (name "Net-(U2-R4IN)") (class "Default")
      (node (ref "J16") (pin "3") (pinfunction "3_3") (pintype "passive"))
      (node (ref "U2") (pin "16") (pinfunction "R4IN_16") (pintype "input"))
    )
    (net (code "56") (name "Net-(U2-T1OUT)") (class "Default")
      (node (ref "J13") (pin "1") (pinfunction "1_1") (pintype "passive"))
      (node (ref "U2") (pin "2") (pinfunction "T1OUT_2") (pintype "output"))
    )
    (net (code "57") (name "Net-(U2-T2OUT)") (class "Default")
      (node (ref "J14") (pin "1") (pinfunction "1_1") (pintype "passive"))
      (node (ref "U2") (pin "1") (pinfunction "T2OUT_1") (pintype "output"))
    )
    (net (code "58") (name "Net-(U2-T3OUT)") (class "Default")
      (node (ref "J15") (pin "1") (pinfunction "1_1") (pintype "passive"))
      (node (ref "U2") (pin "24") (pinfunction "T3OUT_24") (pintype "output"))
    )
    (net (code "59") (name "Net-(U2-T4OUT)") (class "Default")
      (node (ref "J16") (pin "1") (pinfunction "1_1") (pintype "passive"))
      (node (ref "U2") (pin "20") (pinfunction "T4OUT_20") (pintype "output"))
    )
    (net (code "60") (name "Net-(U2-V+)") (class "Default")
      (node (ref "C8") (pin "2") (pinfunction "2_2") (pintype "passive"))
      (node (ref "U2") (pin "11") (pinfunction "V+_11") (pintype "passive"))
    )
    (net (code "61") (name "Net-(U2-V-)") (class "Default")
      (node (ref "C9") (pin "2") (pinfunction "2_2") (pintype "passive"))
      (node (ref "U2") (pin "15") (pinfunction "V-_15") (pintype "passive"))
    )
    (net (code "62") (name "Net-(U3-RX0)") (class "Default")
      (node (ref "J1") (pin "2") (pinfunction "2_2") (pintype "passive"))
      (node (ref "U3") (pin "17") (pinfunction "RX0_17") (pintype "passive"))
    )
    (net (code "63") (name "Net-(U3-RX1)") (class "Default")
      (node (ref "J3") (pin "2") (pinfunction "2_2") (pintype "passive"))
      (node (ref "U3") (pin "25") (pinfunction "RX1_25") (pintype "passive"))
    )
    (net (code "64") (name "Net-(U3-RX2)") (class "Default")
      (node (ref "J5") (pin "2") (pinfunction "2_2") (pintype "passive"))
      (node (ref "U3") (pin "33") (pinfunction "RX2_33") (pintype "passive"))
    )
    (net (code "65") (name "Net-(U3-RX3)") (class "Default")
      (node (ref "J7") (pin "2") (pinfunction "2_2") (pintype "passive"))
      (node (ref "U3") (pin "41") (pinfunction "RX3_41") (pintype "passive"))
    )
    (net (code "66") (name "Net-(U3-TX0)") (class "Default")
      (node (ref "J2") (pin "2") (pinfunction "2_2") (pintype "passive"))
      (node (ref "U3") (pin "18") (pinfunction "TX0_18") (pintype "passive"))
    )
    (net (code "67") (name "Net-(U3-TX1)") (class "Default")
      (node (ref "J4") (pin "2") (pinfunction "2_2") (pintype "passive"))
      (node (ref "U3") (pin "26") (pinfunction "TX1_26") (pintype "passive"))
    )
    (net (code "68") (name "Net-(U3-TX2)") (class "Default")
      (node (ref "J6") (pin "2") (pinfunction "2_2") (pintype "passive"))
      (node (ref "U3") (pin "34") (pinfunction "TX2_34") (pintype "passive"))
    )
    (net (code "69") (name "Net-(U3-TX3)") (class "Default")
      (node (ref "J8") (pin "2") (pinfunction "2_2") (pintype "passive"))
      (node (ref "U3") (pin "42") (pinfunction "TX3_42") (pintype "passive"))
    )
    (net (code "70") (name "Net-(U3-V_18)") (class "Default")
      (node (ref "C10") (pin "2") (pinfunction "2_2") (pintype "passive"))
      (node (ref "U3") (pin "48") (pinfunction "V_18_48") (pintype "passive"))
    )
    (net (code "71") (name "Net-(U3-XIN)") (class "Default")
      (node (ref "U3") (pin "45") (pinfunction "XIN_45") (pintype "passive"))
      (node (ref "Y1") (pin "1") (pinfunction "1_1") (pintype "passive"))
    )
    (net (code "72") (name "Net-(U3-XOUT)") (class "Default")
      (node (ref "U3") (pin "44") (pinfunction "XOUT_44") (pintype "passive"))
      (node (ref "Y1") (pin "2") (pinfunction "2_2") (pintype "passive"))
    )
    (net (code "73") (name "Net-(U3-~{IRQ})") (class "Default")
      (node (ref "R7") (pin "2") (pinfunction "2_2") (pintype "passive"))
      (node (ref "U3") (pin "7") (pinfunction "~{IRQ}_7") (pintype "passive"))
      (node (ref "X3") (pin "9") (pinfunction "9_9") (pintype "passive"))
    )
    (net (code "74") (name "Net-(U3-~{RST})") (class "Default")
      (node (ref "R8") (pin "1") (pinfunction "1_1") (pintype "passive"))
      (node (ref "U3") (pin "8") (pinfunction "~{RST}_8") (pintype "passive"))
      (node (ref "X3") (pin "8") (pinfunction "8_8") (pintype "passive"))
    )
    (net (code "75") (name "Net-(U4-C1+)") (class "Default")
      (node (ref "C14") (pin "2") (pinfunction "2_2") (pintype "passive"))
      (node (ref "U4") (pin "10") (pinfunction "C1+_10") (pintype "passive"))
    )
    (net (code "76") (name "Net-(U4-C1-)") (class "Default")
      (node (ref "C14") (pin "1") (pinfunction "1_1") (pintype "passive"))
      (node (ref "U4") (pin "12") (pinfunction "C1-_12") (pintype "passive"))
    )
    (net (code "77") (name "Net-(U4-C2+)") (class "Default")
      (node (ref "C15") (pin "2") (pinfunction "2_2") (pintype "passive"))
      (node (ref "U4") (pin "13") (pinfunction "C2+_13") (pintype "passive"))
    )
    (net (code "78") (name "Net-(U4-C2-)") (class "Default")
      (node (ref "C15") (pin "1") (pinfunction "1_1") (pintype "passive"))
      (node (ref "U4") (pin "14") (pinfunction "C2-_14") (pintype "passive"))
    )
    (net (code "79") (name "Net-(U4-R1IN)") (class "Default")
      (node (ref "J9") (pin "3") (pinfunction "3_3") (pintype "passive"))
      (node (ref "R15") (pin "2") (pinfunction "2_2") (pintype "passive"))
      (node (ref "U4") (pin "7") (pinfunction "R1IN_7") (pintype "input"))
    )
    (net (code "80") (name "Net-(U4-R2IN)") (class "Default")
      (node (ref "J10") (pin "3") (pinfunction "3_3") (pintype "passive"))
      (node (ref "R17") (pin "2") (pinfunction "2_2") (pintype "passive"))
      (node (ref "U4") (pin "3") (pinfunction "R2IN_3") (pintype "input"))
    )
    (net (code "81") (name "Net-(U4-R3IN)") (class "Default")
      (node (ref "J11") (pin "3") (pinfunction "3_3") (pintype "passive"))
      (node (ref "R19") (pin "2") (pinfunction "2_2") (pintype "passive"))
      (node (ref "U4") (pin "23") (pinfunction "R3IN_23") (pintype "input"))
    )
    (net (code "82") (name "Net-(U4-R4IN)") (class "Default")
      (node (ref "J12") (pin "3") (pinfunction "3_3") (pintype "passive"))
      (node (ref "R21") (pin "2") (pinfunction "2_2") (pintype "passive"))
      (node (ref "U4") (pin "16") (pinfunction "R4IN_16") (pintype "input"))
    )
    (net (code "83") (name "Net-(U4-T1OUT)") (class "Default")
      (node (ref "J9") (pin "1") (pinfunction "1_1") (pintype "passive"))
      (node (ref "R16") (pin "2") (pinfunction "2_2") (pintype "passive"))
      (node (ref "U4") (pin "2") (pinfunction "T1OUT_2") (pintype "output"))
    )
    (net (code "84") (name "Net-(U4-T2OUT)") (class "Default")
      (node (ref "J10") (pin "1") (pinfunction "1_1") (pintype "passive"))
      (node (ref "R18") (pin "2") (pinfunction "2_2") (pintype "passive"))
      (node (ref "U4") (pin "1") (pinfunction "T2OUT_1") (pintype "output"))
    )
    (net (code "85") (name "Net-(U4-T3OUT)") (class "Default")
      (node (ref "J11") (pin "1") (pinfunction "1_1") (pintype "passive"))
      (node (ref "R20") (pin "2") (pinfunction "2_2") (pintype "passive"))
      (node (ref "U4") (pin "24") (pinfunction "T3OUT_24") (pintype "output"))
    )
    (net (code "86") (name "Net-(U4-T4OUT)") (class "Default")
      (node (ref "J12") (pin "1") (pinfunction "1_1") (pintype "passive"))
      (node (ref "R22") (pin "2") (pinfunction "2_2") (pintype "passive"))
      (node (ref "U4") (pin "20") (pinfunction "T4OUT_20") (pintype "output"))
    )
    (net (code "87") (name "Net-(U4-V+)") (class "Default")
      (node (ref "C17") (pin "2") (pinfunction "2_2") (pintype "passive"))
      (node (ref "U4") (pin "11") (pinfunction "V+_11") (pintype "passive"))
    )
    (net (code "88") (name "Net-(U4-V-)") (class "Default")
      (node (ref "C18") (pin "2") (pinfunction "2_2") (pintype "passive"))
      (node (ref "U4") (pin "15") (pinfunction "V-_15") (pintype "passive"))
    )
    (net (code "89") (name "Net-(U4-VCC)") (class "Default")
      (node (ref "C16") (pin "1") (pinfunction "1_1") (pintype "passive"))
      (node (ref "C17") (pin "1") (pinfunction "1_1") (pintype "passive"))
      (node (ref "R23") (pin "1") (pinfunction "1_1") (pintype "passive"))
      (node (ref "U4") (pin "9") (pinfunction "VCC_9") (pintype "passive"))
    )
    (net (code "90") (name "Net-(U5-RXD_ECI)") (class "Default")
      (node (ref "J6") (pin "3") (pinfunction "3_3") (pintype "passive"))
      (node (ref "U5") (pin "12") (pinfunction "RXD_ECI_12") (pintype "passive"))
    )
    (net (code "91") (name "Net-(U5-RXD_SCI)") (class "Default")
      (node (ref "J8") (pin "3") (pinfunction "3_3") (pintype "passive"))
      (node (ref "U5") (pin "20") (pinfunction "RXD_SCI_20") (pintype "passive"))
    )
    (net (code "92") (name "Net-(U5-TXD_ECI)") (class "Default")
      (node (ref "J5") (pin "3") (pinfunction "3_3") (pintype "passive"))
      (node (ref "U5") (pin "13") (pinfunction "TXD_ECI_13") (pintype "passive"))
    )
    (net (code "93") (name "Net-(U5-TXD_SCI)") (class "Default")
      (node (ref "J7") (pin "3") (pinfunction "3_3") (pintype "passive"))
      (node (ref "U5") (pin "21") (pinfunction "TXD_SCI_21") (pintype "passive"))
    )
    (net (code "94") (name "Net-(U5-VBUS)") (class "Default")
      (node (ref "R2") (pin "2") (pinfunction "2_2") (pintype "passive"))
      (node (ref "R3") (pin "2") (pinfunction "2_2") (pintype "passive"))
      (node (ref "U5") (pin "8") (pinfunction "VBUS_8") (pintype "passive"))
    )
    (net (code "95") (name "Net-(U5-~{SUSP}{slash}RI_ECI)") (class "Default")
      (node (ref "R13") (pin "2") (pinfunction "2_2") (pintype "passive"))
      (node (ref "U5") (pin "17") (pinfunction "~{SUSP}/RI_ECI_17") (pintype "passive"))
    )
    (net (code "96") (name "Net-(U5-~{SUSP}{slash}RI_SCI)") (class "Default")
      (node (ref "R14") (pin "1") (pinfunction "1_1") (pintype "passive"))
      (node (ref "U5") (pin "1") (pinfunction "~{SUSP}/RI_SCI_1") (pintype "passive"))
    )
    (net (code "97") (name "Net-(U6-RXD_ECI)") (class "Default")
      (node (ref "J2") (pin "3") (pinfunction "3_3") (pintype "passive"))
      (node (ref "U6") (pin "12") (pinfunction "RXD_ECI_12") (pintype "passive"))
    )
    (net (code "98") (name "Net-(U6-RXD_SCI)") (class "Default")
      (node (ref "J4") (pin "3") (pinfunction "3_3") (pintype "passive"))
      (node (ref "U6") (pin "20") (pinfunction "RXD_SCI_20") (pintype "passive"))
    )
    (net (code "99") (name "Net-(U6-TXD_ECI)") (class "Default")
      (node (ref "J1") (pin "3") (pinfunction "3_3") (pintype "passive"))
      (node (ref "U6") (pin "13") (pinfunction "TXD_ECI_13") (pintype "passive"))
    )
    (net (code "100") (name "Net-(U6-TXD_SCI)") (class "Default")
      (node (ref "J3") (pin "3") (pinfunction "3_3") (pintype "passive"))
      (node (ref "U6") (pin "21") (pinfunction "TXD_SCI_21") (pintype "passive"))
    )
    (net (code "101") (name "Net-(U6-VBUS)") (class "Default")
      (node (ref "R5") (pin "2") (pinfunction "2_2") (pintype "passive"))
      (node (ref "R6") (pin "2") (pinfunction "2_2") (pintype "passive"))
      (node (ref "U6") (pin "8") (pinfunction "VBUS_8") (pintype "passive"))
    )
    (net (code "102") (name "Net-(U6-~{SUSP}{slash}RI_ECI)") (class "Default")
      (node (ref "R11") (pin "2") (pinfunction "2_2") (pintype "passive"))
      (node (ref "U6") (pin "17") (pinfunction "~{SUSP}/RI_ECI_17") (pintype "passive"))
    )
    (net (code "103") (name "Net-(U6-~{SUSP}{slash}RI_SCI)") (class "Default")
      (node (ref "R12") (pin "1") (pinfunction "1_1") (pintype "passive"))
      (node (ref "U6") (pin "1") (pinfunction "~{SUSP}/RI_SCI_1") (pintype "passive"))
    )
    (net (code "104") (name "Net-(X1-Shield)") (class "Default")
      (node (ref "L2") (pin "1") (pinfunction "1_1") (pintype "passive"))
      (node (ref "X1") (pin "0") (pinfunction "Shield_0") (pintype "passive"))
    )
    (net (code "105") (name "Net-(X2-Shield)") (class "Default")
      (node (ref "L4") (pin "1") (pinfunction "1_1") (pintype "passive"))
      (node (ref "X2") (pin "0") (pinfunction "Shield_0") (pintype "passive"))
    )
    (net (code "106") (name "V_U1") (class "Default")
      (node (ref "C21") (pin "2") (pinfunction "2_2") (pintype "passive"))
      (node (ref "D4") (pin "1") (pinfunction "A_1") (pintype "passive"))
      (node (ref "L1") (pin "2") (pinfunction "2_2") (pintype "passive"))
      (node (ref "R2") (pin "1") (pinfunction "1_1") (pintype "passive"))
    )
    (net (code "107") (name "V_U2") (class "Default")
      (node (ref "C24") (pin "2") (pinfunction "2_2") (pintype "passive"))
      (node (ref "D3") (pin "1") (pinfunction "A_1") (pintype "passive"))
      (node (ref "L3") (pin "2") (pinfunction "2_2") (pintype "passive"))
      (node (ref "R6") (pin "1") (pinfunction "1_1") (pintype "passive"))
    )
    (net (code "108") (name "unconnected-(D5-K1-Pad2)") (class "Default")
      (node (ref "D5") (pin "2") (pinfunction "K1_2") (pintype "passive"))
    )
    (net (code "109") (name "unconnected-(D5-K3-Pad4)") (class "Default")
      (node (ref "D5") (pin "4") (pinfunction "K3_4") (pintype "passive"))
    )
    (net (code "110") (name "unconnected-(D8-K2-Pad3)") (class "Default")
      (node (ref "D8") (pin "3") (pinfunction "K2_3") (pintype "passive"))
    )
    (net (code "111") (name "unconnected-(U1-GPIO0-Pad11)") (class "Default")
      (node (ref "U1") (pin "11") (pinfunction "GPIO0_11") (pintype "passive"))
    )
    (net (code "112") (name "unconnected-(U1-GPIO1-Pad12)") (class "Default")
      (node (ref "U1") (pin "12") (pinfunction "GPIO1_12") (pintype "passive"))
    )
    (net (code "113") (name "unconnected-(U1-GPIO2-Pad13)") (class "Default")
      (node (ref "U1") (pin "13") (pinfunction "GPIO2_13") (pintype "passive"))
    )
    (net (code "114") (name "unconnected-(U1-GPIO3-Pad14)") (class "Default")
      (node (ref "U1") (pin "14") (pinfunction "GPIO3_14") (pintype "passive"))
    )
    (net (code "115") (name "unconnected-(U1-GPIO4-Pad19)") (class "Default")
      (node (ref "U1") (pin "19") (pinfunction "GPIO4_19") (pintype "passive"))
    )
    (net (code "116") (name "unconnected-(U1-GPIO5-Pad20)") (class "Default")
      (node (ref "U1") (pin "20") (pinfunction "GPIO5_20") (pintype "passive"))
    )
    (net (code "117") (name "unconnected-(U1-GPIO6-Pad21)") (class "Default")
      (node (ref "U1") (pin "21") (pinfunction "GPIO6_21") (pintype "passive"))
    )
    (net (code "118") (name "unconnected-(U1-GPIO7-Pad22)") (class "Default")
      (node (ref "U1") (pin "22") (pinfunction "GPIO7_22") (pintype "passive"))
    )
    (net (code "119") (name "unconnected-(U1-GPIO8-Pad27)") (class "Default")
      (node (ref "U1") (pin "27") (pinfunction "GPIO8_27") (pintype "passive"))
    )
    (net (code "120") (name "unconnected-(U1-GPIO9-Pad28)") (class "Default")
      (node (ref "U1") (pin "28") (pinfunction "GPIO9_28") (pintype "passive"))
    )
    (net (code "121") (name "unconnected-(U1-GPIO10-Pad29)") (class "Default")
      (node (ref "U1") (pin "29") (pinfunction "GPIO10_29") (pintype "passive"))
    )
    (net (code "122") (name "unconnected-(U1-GPIO11-Pad30)") (class "Default")
      (node (ref "U1") (pin "30") (pinfunction "GPIO11_30") (pintype "passive"))
    )
    (net (code "123") (name "unconnected-(U1-GPIO12-Pad35)") (class "Default")
      (node (ref "U1") (pin "35") (pinfunction "GPIO12_35") (pintype "passive"))
    )
    (net (code "124") (name "unconnected-(U1-GPIO13-Pad36)") (class "Default")
      (node (ref "U1") (pin "36") (pinfunction "GPIO13_36") (pintype "passive"))
    )
    (net (code "125") (name "unconnected-(U1-GPIO14-Pad37)") (class "Default")
      (node (ref "U1") (pin "37") (pinfunction "GPIO14_37") (pintype "passive"))
    )
    (net (code "126") (name "unconnected-(U1-GPIO15-Pad38)") (class "Default")
      (node (ref "U1") (pin "38") (pinfunction "GPIO15_38") (pintype "passive"))
    )
    (net (code "127") (name "unconnected-(U1-~{CTS0}-Pad16)") (class "Default")
      (node (ref "U1") (pin "16") (pinfunction "~{CTS0}_16") (pintype "passive"))
    )
    (net (code "128") (name "unconnected-(U1-~{CTS1}-Pad24)") (class "Default")
      (node (ref "U1") (pin "24") (pinfunction "~{CTS1}_24") (pintype "passive"))
    )
    (net (code "129") (name "unconnected-(U1-~{CTS2}-Pad32)") (class "Default")
      (node (ref "U1") (pin "32") (pinfunction "~{CTS2}_32") (pintype "passive"))
    )
    (net (code "130") (name "unconnected-(U1-~{CTS3}-Pad40)") (class "Default")
      (node (ref "U1") (pin "40") (pinfunction "~{CTS3}_40") (pintype "passive"))
    )
    (net (code "131") (name "unconnected-(U1-~{RTS0}-Pad15)") (class "Default")
      (node (ref "U1") (pin "15") (pinfunction "~{RTS0}_15") (pintype "passive"))
    )
    (net (code "132") (name "unconnected-(U1-~{RTS1}-Pad23)") (class "Default")
      (node (ref "U1") (pin "23") (pinfunction "~{RTS1}_23") (pintype "passive"))
    )
    (net (code "133") (name "unconnected-(U1-~{RTS2}-Pad31)") (class "Default")
      (node (ref "U1") (pin "31") (pinfunction "~{RTS2}_31") (pintype "passive"))
    )
    (net (code "134") (name "unconnected-(U1-~{RTS3}-Pad39)") (class "Default")
      (node (ref "U1") (pin "39") (pinfunction "~{RTS3}_39") (pintype "passive"))
    )
    (net (code "135") (name "unconnected-(U3-GPIO0-Pad11)") (class "Default")
      (node (ref "U3") (pin "11") (pinfunction "GPIO0_11") (pintype "passive"))
    )
    (net (code "136") (name "unconnected-(U3-GPIO1-Pad12)") (class "Default")
      (node (ref "U3") (pin "12") (pinfunction "GPIO1_12") (pintype "passive"))
    )
    (net (code "137") (name "unconnected-(U3-GPIO2-Pad13)") (class "Default")
      (node (ref "U3") (pin "13") (pinfunction "GPIO2_13") (pintype "passive"))
    )
    (net (code "138") (name "unconnected-(U3-GPIO3-Pad14)") (class "Default")
      (node (ref "U3") (pin "14") (pinfunction "GPIO3_14") (pintype "passive"))
    )
    (net (code "139") (name "unconnected-(U3-GPIO4-Pad19)") (class "Default")
      (node (ref "U3") (pin "19") (pinfunction "GPIO4_19") (pintype "passive"))
    )
    (net (code "140") (name "unconnected-(U3-GPIO5-Pad20)") (class "Default")
      (node (ref "U3") (pin "20") (pinfunction "GPIO5_20") (pintype "passive"))
    )
    (net (code "141") (name "unconnected-(U3-GPIO6-Pad21)") (class "Default")
      (node (ref "U3") (pin "21") (pinfunction "GPIO6_21") (pintype "passive"))
    )
    (net (code "142") (name "unconnected-(U3-GPIO7-Pad22)") (class "Default")
      (node (ref "U3") (pin "22") (pinfunction "GPIO7_22") (pintype "passive"))
    )
    (net (code "143") (name "unconnected-(U3-GPIO8-Pad27)") (class "Default")
      (node (ref "U3") (pin "27") (pinfunction "GPIO8_27") (pintype "passive"))
    )
    (net (code "144") (name "unconnected-(U3-GPIO9-Pad28)") (class "Default")
      (node (ref "U3") (pin "28") (pinfunction "GPIO9_28") (pintype "passive"))
    )
    (net (code "145") (name "unconnected-(U3-GPIO10-Pad29)") (class "Default")
      (node (ref "U3") (pin "29") (pinfunction "GPIO10_29") (pintype "passive"))
    )
    (net (code "146") (name "unconnected-(U3-GPIO11-Pad30)") (class "Default")
      (node (ref "U3") (pin "30") (pinfunction "GPIO11_30") (pintype "passive"))
    )
    (net (code "147") (name "unconnected-(U3-GPIO12-Pad35)") (class "Default")
      (node (ref "U3") (pin "35") (pinfunction "GPIO12_35") (pintype "passive"))
    )
    (net (code "148") (name "unconnected-(U3-GPIO13-Pad36)") (class "Default")
      (node (ref "U3") (pin "36") (pinfunction "GPIO13_36") (pintype "passive"))
    )
    (net (code "149") (name "unconnected-(U3-GPIO14-Pad37)") (class "Default")
      (node (ref "U3") (pin "37") (pinfunction "GPIO14_37") (pintype "passive"))
    )
    (net (code "150") (name "unconnected-(U3-GPIO15-Pad38)") (class "Default")
      (node (ref "U3") (pin "38") (pinfunction "GPIO15_38") (pintype "passive"))
    )
    (net (code "151") (name "unconnected-(U3-~{CTS0}-Pad16)") (class "Default")
      (node (ref "U3") (pin "16") (pinfunction "~{CTS0}_16") (pintype "passive"))
    )
    (net (code "152") (name "unconnected-(U3-~{CTS1}-Pad24)") (class "Default")
      (node (ref "U3") (pin "24") (pinfunction "~{CTS1}_24") (pintype "passive"))
    )
    (net (code "153") (name "unconnected-(U3-~{CTS2}-Pad32)") (class "Default")
      (node (ref "U3") (pin "32") (pinfunction "~{CTS2}_32") (pintype "passive"))
    )
    (net (code "154") (name "unconnected-(U3-~{CTS3}-Pad40)") (class "Default")
      (node (ref "U3") (pin "40") (pinfunction "~{CTS3}_40") (pintype "passive"))
    )
    (net (code "155") (name "unconnected-(U3-~{RTS0}-Pad15)") (class "Default")
      (node (ref "U3") (pin "15") (pinfunction "~{RTS0}_15") (pintype "passive"))
    )
    (net (code "156") (name "unconnected-(U3-~{RTS1}-Pad23)") (class "Default")
      (node (ref "U3") (pin "23") (pinfunction "~{RTS1}_23") (pintype "passive"))
    )
    (net (code "157") (name "unconnected-(U3-~{RTS2}-Pad31)") (class "Default")
      (node (ref "U3") (pin "31") (pinfunction "~{RTS2}_31") (pintype "passive"))
    )
    (net (code "158") (name "unconnected-(U3-~{RTS3}-Pad39)") (class "Default")
      (node (ref "U3") (pin "39") (pinfunction "~{RTS3}_39") (pintype "passive"))
    )
    (net (code "159") (name "unconnected-(U5-CTS_ECI-Pad10)") (class "Default")
      (node (ref "U5") (pin "10") (pinfunction "CTS_ECI_10") (pintype "passive"))
    )
    (net (code "160") (name "unconnected-(U5-CTS_SCI-Pad18)") (class "Default")
      (node (ref "U5") (pin "18") (pinfunction "CTS_SCI_18") (pintype "passive"))
    )
    (net (code "161") (name "unconnected-(U5-GPIO0_DCD_SCI-Pad24)") (class "Default")
      (node (ref "U5") (pin "24") (pinfunction "GPIO0_DCD_SCI_24") (pintype "passive"))
    )
    (net (code "162") (name "unconnected-(U5-GPIO0_DTR_ECI-Pad15)") (class "Default")
      (node (ref "U5") (pin "15") (pinfunction "GPIO0_DTR_ECI_15") (pintype "passive"))
    )
    (net (code "163") (name "unconnected-(U5-GPIO1_DSR_ECI-Pad14)") (class "Default")
      (node (ref "U5") (pin "14") (pinfunction "GPIO1_DSR_ECI_14") (pintype "passive"))
    )
    (net (code "164") (name "unconnected-(U5-GPIO1_DTR_SCI-Pad23)") (class "Default")
      (node (ref "U5") (pin "23") (pinfunction "GPIO1_DTR_SCI_23") (pintype "passive"))
    )
    (net (code "165") (name "unconnected-(U5-GPIO2_DSR_SCI-Pad22)") (class "Default")
      (node (ref "U5") (pin "22") (pinfunction "GPIO2_DSR_SCI_22") (pintype "passive"))
    )
    (net (code "166") (name "unconnected-(U5-NC{slash}DCD_ECI{slash}VPP-Pad16)") (class "Default")
      (node (ref "U5") (pin "16") (pinfunction "NC/DCD_ECI/VPP_16") (pintype "passive"))
    )
    (net (code "167") (name "unconnected-(U5-RTS_ECI-Pad11)") (class "Default")
      (node (ref "U5") (pin "11") (pinfunction "RTS_ECI_11") (pintype "passive"))
    )
    (net (code "168") (name "unconnected-(U5-RTS_SCI-Pad19)") (class "Default")
      (node (ref "U5") (pin "19") (pinfunction "RTS_SCI_19") (pintype "passive"))
    )
    (net (code "169") (name "unconnected-(U6-CTS_ECI-Pad10)") (class "Default")
      (node (ref "U6") (pin "10") (pinfunction "CTS_ECI_10") (pintype "passive"))
    )
    (net (code "170") (name "unconnected-(U6-CTS_SCI-Pad18)") (class "Default")
      (node (ref "U6") (pin "18") (pinfunction "CTS_SCI_18") (pintype "passive"))
    )
    (net (code "171") (name "unconnected-(U6-GPIO0_DCD_SCI-Pad24)") (class "Default")
      (node (ref "U6") (pin "24") (pinfunction "GPIO0_DCD_SCI_24") (pintype "passive"))
    )
    (net (code "172") (name "unconnected-(U6-GPIO0_DTR_ECI-Pad15)") (class "Default")
      (node (ref "U6") (pin "15") (pinfunction "GPIO0_DTR_ECI_15") (pintype "passive"))
    )
    (net (code "173") (name "unconnected-(U6-GPIO1_DSR_ECI-Pad14)") (class "Default")
      (node (ref "U6") (pin "14") (pinfunction "GPIO1_DSR_ECI_14") (pintype "passive"))
    )
    (net (code "174") (name "unconnected-(U6-GPIO1_DTR_SCI-Pad23)") (class "Default")
      (node (ref "U6") (pin "23") (pinfunction "GPIO1_DTR_SCI_23") (pintype "passive"))
    )
    (net (code "175") (name "unconnected-(U6-GPIO2_DSR_SCI-Pad22)") (class "Default")
      (node (ref "U6") (pin "22") (pinfunction "GPIO2_DSR_SCI_22") (pintype "passive"))
    )
    (net (code "176") (name "unconnected-(U6-NC{slash}DCD_ECI{slash}VPP-Pad16)") (class "Default")
      (node (ref "U6") (pin "16") (pinfunction "NC/DCD_ECI/VPP_16") (pintype "passive"))
    )
    (net (code "177") (name "unconnected-(U6-RTS_ECI-Pad11)") (class "Default")
      (node (ref "U6") (pin "11") (pinfunction "RTS_ECI_11") (pintype "passive"))
    )
    (net (code "178") (name "unconnected-(U6-RTS_SCI-Pad19)") (class "Default")
      (node (ref "U6") (pin "19") (pinfunction "RTS_SCI_19") (pintype "passive"))
    )
    (net (code "179") (name "unconnected-(X3-14{slash}A0-Pad14)") (class "Default")
      (node (ref "X3") (pin "14") (pinfunction "14/A0_14") (pintype "passive"))
    )
    (net (code "180") (name "unconnected-(X3-18{slash}A4-Pad18)") (class "Default")
      (node (ref "X3") (pin "18") (pinfunction "18/A4_18") (pintype "passive"))
    )
    (net (code "181") (name "unconnected-(X3-22{slash}A8-Pad22)") (class "Default")
      (node (ref "X3") (pin "22") (pinfunction "22/A8_22") (pintype "passive"))
    )
    (net (code "182") (name "unconnected-(X3-23{slash}A9-Pad23)") (class "Default")
      (node (ref "X3") (pin "23") (pinfunction "23/A9_23") (pintype "passive"))
    )
    (net (code "183") (name "unconnected-(X3-A14{slash}DAC-PadA14)") (class "Default")
      (node (ref "X3") (pin "A14") (pinfunction "A14/DAC_A14") (pintype "passive"))
    )
    (net (code "184") (name "unconnected-(X3-Pad0)") (class "Default")
      (node (ref "X3") (pin "0") (pinfunction "0_0") (pintype "passive"))
    )
    (net (code "185") (name "unconnected-(X3-Pad1)") (class "Default")
      (node (ref "X3") (pin "1") (pinfunction "1_1") (pintype "passive"))
    )
    (net (code "186") (name "unconnected-(X3-Pad2)") (class "Default")
      (node (ref "X3") (pin "2") (pinfunction "2_2") (pintype "passive"))
    )
    (net (code "187") (name "unconnected-(X3-Pad3)") (class "Default")
      (node (ref "X3") (pin "3") (pinfunction "3_3") (pintype "passive"))
    )
    (net (code "188") (name "unconnected-(X3-Pad4)") (class "Default")
      (node (ref "X3") (pin "4") (pinfunction "4_4") (pintype "passive"))
    )
    (net (code "189") (name "unconnected-(X3-Pad5)") (class "Default")
      (node (ref "X3") (pin "5") (pinfunction "5_5") (pintype "passive"))
    )
    (net (code "190") (name "unconnected-(X3-PadAGND)") (class "Default")
      (node (ref "X3") (pin "AGND") (pinfunction "AGND_AGND") (pintype "passive"))
    )
    (net (code "191") (name "unconnected-(X3-PadProgram)") (class "Default")
      (node (ref "X3") (pin "Program") (pinfunction "Program_Program") (pintype "passive"))
    )
    (net (code "192") (name "unconnected-(X3-PadVBat)") (class "Default")
      (node (ref "X3") (pin "VBat") (pinfunction "VBat_VBat") (pintype "passive"))
    )
  )
)
